# stirrer.net
KiCad netlist of a schematic drawn in EAGLE
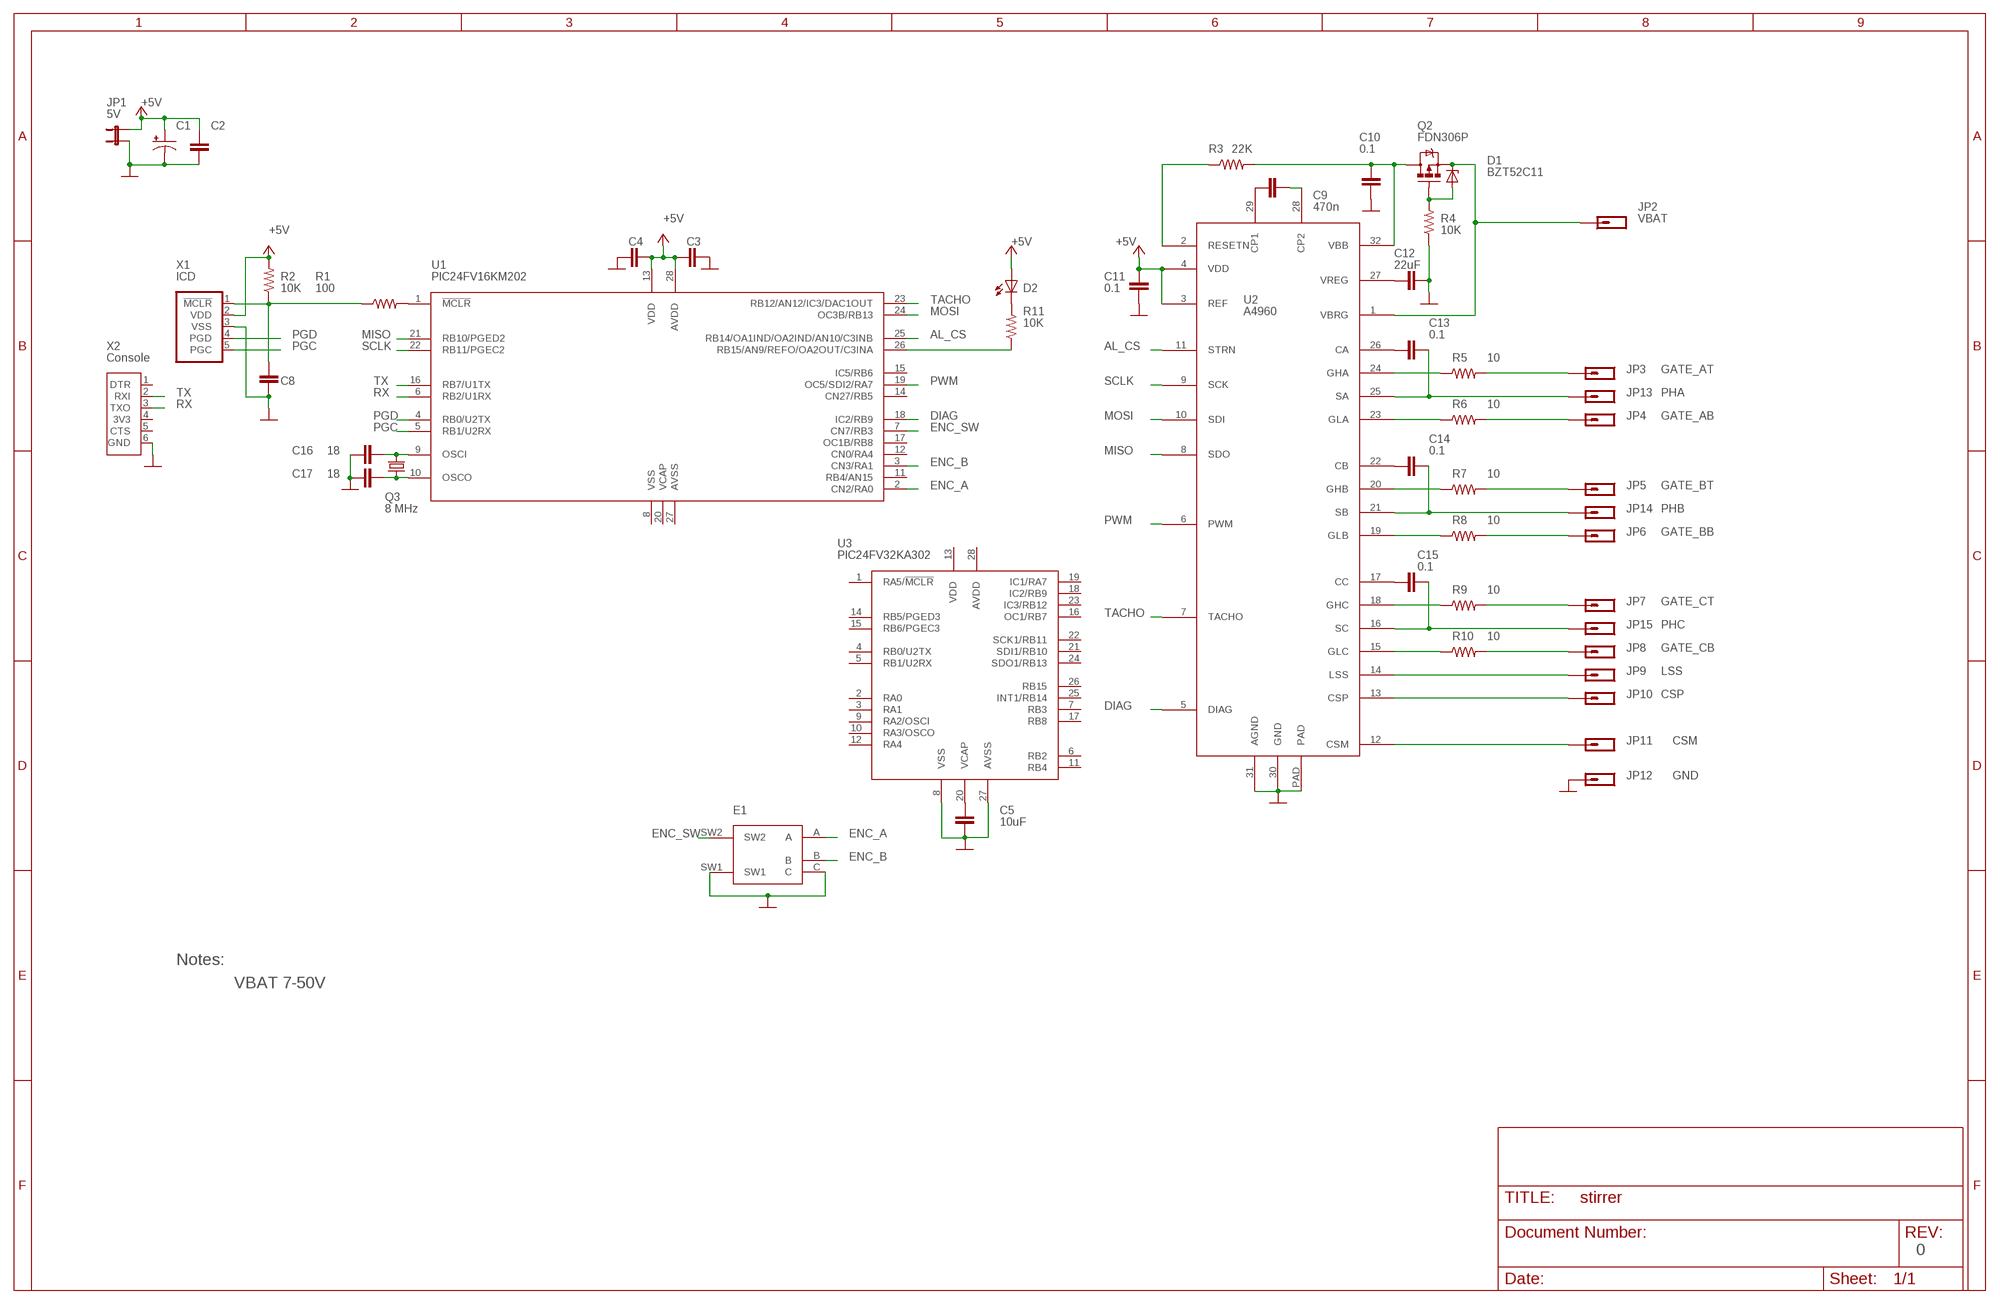
[diagram p0: schematic, sheet 1]

(export (version "E")
  (design (tool "Eeschema 10.0.6"))
  (components
    (comp (ref "C1")
      (value "CAP_POL-RAD8")
      (footprint "eagle-import:CAP_RAD_8MM")
      (libsource (lib "eagle-import") (part "CAP_POL-RAD8"))
    )
    (comp (ref "C2")
      (value "CAP0603")
      (footprint "eagle-import:0603")
      (libsource (lib "eagle-import") (part "CAP0603"))
    )
    (comp (ref "C3")
      (value "0.1uF")
      (footprint "eagle-import:0603")
      (libsource (lib "eagle-import") (part "C-0603"))
    )
    (comp (ref "C4")
      (value "0.1uF")
      (footprint "eagle-import:0603")
      (libsource (lib "eagle-import") (part "C-0603"))
    )
    (comp (ref "C5")
      (value "10uF")
      (footprint "eagle-import:0603")
      (libsource (lib "eagle-import") (part "C-0603"))
    )
    (comp (ref "C8")
      (value "0.1uF")
      (footprint "eagle-import:0603")
      (libsource (lib "eagle-import") (part "C-0603"))
    )
    (comp (ref "C9")
      (value "470n")
      (footprint "eagle-import:0603")
      (libsource (lib "eagle-import") (part "C-0603"))
    )
    (comp (ref "C10")
      (value "0.1")
      (footprint "eagle-import:0603")
      (libsource (lib "eagle-import") (part "C-0603"))
    )
    (comp (ref "C11")
      (value "0.1")
      (footprint "eagle-import:0603")
      (libsource (lib "eagle-import") (part "C-0603"))
    )
    (comp (ref "C12")
      (value "22uF")
      (footprint "eagle-import:1206")
      (libsource (lib "eagle-import") (part "CAP1206"))
    )
    (comp (ref "C13")
      (value "0.1")
      (footprint "eagle-import:0603")
      (libsource (lib "eagle-import") (part "C-0603"))
    )
    (comp (ref "C14")
      (value "0.1")
      (footprint "eagle-import:0603")
      (libsource (lib "eagle-import") (part "C-0603"))
    )
    (comp (ref "C15")
      (value "0.1")
      (footprint "eagle-import:0603")
      (libsource (lib "eagle-import") (part "C-0603"))
    )
    (comp (ref "C16")
      (value "18")
      (footprint "eagle-import:0603")
      (libsource (lib "eagle-import") (part "C-0603"))
    )
    (comp (ref "C17")
      (value "18")
      (footprint "eagle-import:0603")
      (libsource (lib "eagle-import") (part "C-0603"))
    )
    (comp (ref "D1")
      (value "BZT52C11")
      (footprint "eagle-import:SOD-123")
      (libsource (lib "eagle-import") (part "ZENER-SOD-123"))
    )
    (comp (ref "D2")
      (value "LED5MM")
      (footprint "eagle-import:LED5MM")
      (libsource (lib "eagle-import") (part "LED5MM"))
    )
    (comp (ref "E1")
      (value "ROTARY_ENCODER_SWITCH-LUT")
      (footprint "eagle-import:PEC12-LUT")
      (libsource (lib "eagle-import") (part "ROTARY_ENCODER_SWITCH-LUT"))
    )
    (comp (ref "JP1")
      (value "5V")
      (footprint "eagle-import:1X02")
      (libsource (lib "eagle-import") (part "JP1EPTH"))
    )
    (comp (ref "JP2")
      (value "VBAT")
      (footprint "eagle-import:1X01_TT")
      (libsource (lib "eagle-import") (part "M01-TT"))
    )
    (comp (ref "JP3")
      (value "GATE_AT")
      (footprint "eagle-import:1X01_TT")
      (libsource (lib "eagle-import") (part "M01-TT"))
    )
    (comp (ref "JP4")
      (value "GATE_AB")
      (footprint "eagle-import:1X01_TT")
      (libsource (lib "eagle-import") (part "M01-TT"))
    )
    (comp (ref "JP5")
      (value "GATE_BT")
      (footprint "eagle-import:1X01_TT")
      (libsource (lib "eagle-import") (part "M01-TT"))
    )
    (comp (ref "JP6")
      (value "GATE_BB")
      (footprint "eagle-import:1X01_TT")
      (libsource (lib "eagle-import") (part "M01-TT"))
    )
    (comp (ref "JP7")
      (value "GATE_CT")
      (footprint "eagle-import:1X01_TT")
      (libsource (lib "eagle-import") (part "M01-TT"))
    )
    (comp (ref "JP8")
      (value "GATE_CB")
      (footprint "eagle-import:1X01_TT")
      (libsource (lib "eagle-import") (part "M01-TT"))
    )
    (comp (ref "JP9")
      (value "LSS")
      (footprint "eagle-import:1X01_TT")
      (libsource (lib "eagle-import") (part "M01-TT"))
    )
    (comp (ref "JP10")
      (value "CSP")
      (footprint "eagle-import:1X01_TT")
      (libsource (lib "eagle-import") (part "M01-TT"))
    )
    (comp (ref "JP11")
      (value "CSM")
      (footprint "eagle-import:1X01_TT")
      (libsource (lib "eagle-import") (part "M01-TT"))
    )
    (comp (ref "JP12")
      (value "GND")
      (footprint "eagle-import:1X01_TT")
      (libsource (lib "eagle-import") (part "M01-TT"))
    )
    (comp (ref "JP13")
      (value "PHA")
      (footprint "eagle-import:1X01_TT")
      (libsource (lib "eagle-import") (part "M01-TT"))
    )
    (comp (ref "JP14")
      (value "PHB")
      (footprint "eagle-import:1X01_TT")
      (libsource (lib "eagle-import") (part "M01-TT"))
    )
    (comp (ref "JP15")
      (value "PHC")
      (footprint "eagle-import:1X01_TT")
      (libsource (lib "eagle-import") (part "M01-TT"))
    )
    (comp (ref "Q2")
      (value "FDN306P")
      (footprint "eagle-import:DPAK")
      (libsource (lib "eagle-import") (part "MOSFET-PCHANNEL-DPAK"))
    )
    (comp (ref "Q3")
      (value "8 MHz")
      (footprint "eagle-import:HC49US")
      (libsource (lib "eagle-import") (part "CRYSTAL_SFEHC49US"))
    )
    (comp (ref "R1")
      (value "100")
      (footprint "eagle-import:0603")
      (libsource (lib "eagle-import") (part "RESISTOR-0603"))
    )
    (comp (ref "R2")
      (value "10K")
      (footprint "eagle-import:0603")
      (libsource (lib "eagle-import") (part "RESISTOR-0603"))
    )
    (comp (ref "R3")
      (value "22K")
      (footprint "eagle-import:0603")
      (libsource (lib "eagle-import") (part "RESISTOR-0603"))
    )
    (comp (ref "R4")
      (value "10K")
      (footprint "eagle-import:0603")
      (libsource (lib "eagle-import") (part "RESISTOR-0603"))
    )
    (comp (ref "R5")
      (value "10")
      (footprint "eagle-import:0603")
      (libsource (lib "eagle-import") (part "RESISTOR-0603"))
    )
    (comp (ref "R6")
      (value "10")
      (footprint "eagle-import:0603")
      (libsource (lib "eagle-import") (part "RESISTOR-0603"))
    )
    (comp (ref "R7")
      (value "10")
      (footprint "eagle-import:0603")
      (libsource (lib "eagle-import") (part "RESISTOR-0603"))
    )
    (comp (ref "R8")
      (value "10")
      (footprint "eagle-import:0603")
      (libsource (lib "eagle-import") (part "RESISTOR-0603"))
    )
    (comp (ref "R9")
      (value "10")
      (footprint "eagle-import:0603")
      (libsource (lib "eagle-import") (part "RESISTOR-0603"))
    )
    (comp (ref "R10")
      (value "10")
      (footprint "eagle-import:0603")
      (libsource (lib "eagle-import") (part "RESISTOR-0603"))
    )
    (comp (ref "R11")
      (value "10K")
      (footprint "eagle-import:0603")
      (libsource (lib "eagle-import") (part "RESISTOR-0603"))
    )
    (comp (ref "U1")
      (value "PIC24FV16KM202")
      (footprint "eagle-import:DIL28-3")
      (libsource (lib "eagle-import") (part "PIC24FX16KM202-DIP"))
    )
    (comp (ref "U2")
      (value "A4960")
      (footprint "eagle-import:LQPF-32")
      (libsource (lib "eagle-import") (part "A4960"))
    )
    (comp (ref "U3")
      (value "PIC24FV32KA302")
      (footprint "eagle-import:DIL28-3")
      (libsource (lib "eagle-import") (part "PIC24FV32KA302_STIR-DIP"))
    )
    (comp (ref "X1")
      (value "ICD")
      (footprint "eagle-import:1X05-TT")
      (libsource (lib "eagle-import") (part "PIC_ICD-TT"))
    )
    (comp (ref "X2")
      (value "Console")
      (footprint "eagle-import:1X06TT")
      (libsource (lib "eagle-import") (part "SERIAL-SFTT"))
    )
  )
  (nets
    (net (code "1") (name "+5V") (class "Default")
      (node (ref "C1") (pin "P") (pinfunction "+_P") (pintype "passive"))
      (node (ref "C11") (pin "2") (pinfunction "2_2") (pintype "passive"))
      (node (ref "C2") (pin "1") (pinfunction "1_1") (pintype "passive"))
      (node (ref "C3") (pin "1") (pinfunction "1_1") (pintype "passive"))
      (node (ref "C4") (pin "2") (pinfunction "2_2") (pintype "passive"))
      (node (ref "D2") (pin "A") (pinfunction "A_A") (pintype "passive"))
      (node (ref "JP1") (pin "2") (pinfunction "2_2") (pintype "passive"))
      (node (ref "R2") (pin "2") (pinfunction "2_2") (pintype "passive"))
      (node (ref "U1") (pin "13") (pinfunction "VDD_13") (pintype "bidirectional"))
      (node (ref "U1") (pin "28") (pinfunction "AVDD_28") (pintype "bidirectional"))
      (node (ref "U2") (pin "3") (pinfunction "REF_3") (pintype "bidirectional"))
      (node (ref "U2") (pin "4") (pinfunction "VDD_4") (pintype "bidirectional"))
      (node (ref "X1") (pin "2") (pinfunction "VDD_2") (pintype "passive"))
    )
    (net (code "2") (name "/AL_CS") (class "Default")
      (node (ref "U1") (pin "25") (pinfunction "RB14/OA1IND/OA2IND/AN10/C3INB_25") (pintype "bidirectional"))
      (node (ref "U2") (pin "11") (pinfunction "STRN_11") (pintype "bidirectional"))
    )
    (net (code "3") (name "/DIAG") (class "Default")
      (node (ref "U1") (pin "18") (pinfunction "IC2/RB9_18") (pintype "bidirectional"))
      (node (ref "U2") (pin "5") (pinfunction "DIAG_5") (pintype "bidirectional"))
    )
    (net (code "4") (name "/ENC_A") (class "Default")
      (node (ref "E1") (pin "A") (pinfunction "A_A") (pintype "passive"))
      (node (ref "U1") (pin "2") (pinfunction "CN2/RA0_2") (pintype "bidirectional"))
    )
    (net (code "5") (name "/ENC_B") (class "Default")
      (node (ref "E1") (pin "B") (pinfunction "B_B") (pintype "passive"))
      (node (ref "U1") (pin "3") (pinfunction "CN3/RA1_3") (pintype "bidirectional"))
    )
    (net (code "6") (name "/ENC_SW") (class "Default")
      (node (ref "E1") (pin "SW2") (pinfunction "SW2_SW2") (pintype "passive"))
      (node (ref "U1") (pin "7") (pinfunction "CN7/RB3_7") (pintype "bidirectional"))
    )
    (net (code "7") (name "/MISO") (class "Default")
      (node (ref "U1") (pin "21") (pinfunction "RB10/PGED2_21") (pintype "bidirectional"))
      (node (ref "U2") (pin "8") (pinfunction "SDO_8") (pintype "bidirectional"))
    )
    (net (code "8") (name "/MOSI") (class "Default")
      (node (ref "U1") (pin "24") (pinfunction "OC3B/RB13_24") (pintype "bidirectional"))
      (node (ref "U2") (pin "10") (pinfunction "SDI_10") (pintype "bidirectional"))
    )
    (net (code "9") (name "/PGC") (class "Default")
      (node (ref "U1") (pin "5") (pinfunction "RB1/U2RX_5") (pintype "bidirectional"))
      (node (ref "X1") (pin "5") (pinfunction "PGC_5") (pintype "passive"))
    )
    (net (code "10") (name "/PGD") (class "Default")
      (node (ref "U1") (pin "4") (pinfunction "RB0/U2TX_4") (pintype "bidirectional"))
      (node (ref "X1") (pin "4") (pinfunction "PGD_4") (pintype "passive"))
    )
    (net (code "11") (name "/PWM") (class "Default")
      (node (ref "U1") (pin "19") (pinfunction "OC5/SDI2/RA7_19") (pintype "bidirectional"))
      (node (ref "U2") (pin "6") (pinfunction "PWM_6") (pintype "bidirectional"))
    )
    (net (code "12") (name "/RX") (class "Default")
      (node (ref "U1") (pin "6") (pinfunction "RB2/U1RX_6") (pintype "bidirectional"))
      (node (ref "X2") (pin "3") (pinfunction "TXO_3") (pintype "bidirectional"))
    )
    (net (code "13") (name "/SCLK") (class "Default")
      (node (ref "U1") (pin "22") (pinfunction "RB11/PGEC2_22") (pintype "bidirectional"))
      (node (ref "U2") (pin "9") (pinfunction "SCK_9") (pintype "bidirectional"))
    )
    (net (code "14") (name "/TACHO") (class "Default")
      (node (ref "U1") (pin "23") (pinfunction "RB12/AN12/IC3/DAC1OUT_23") (pintype "bidirectional"))
      (node (ref "U2") (pin "7") (pinfunction "TACHO_7") (pintype "bidirectional"))
    )
    (net (code "15") (name "/TX") (class "Default")
      (node (ref "U1") (pin "16") (pinfunction "RB7/U1TX_16") (pintype "bidirectional"))
      (node (ref "X2") (pin "2") (pinfunction "RXI_2") (pintype "bidirectional"))
    )
    (net (code "16") (name "GND") (class "Default")
      (node (ref "C1") (pin "N") (pinfunction "-_N") (pintype "passive"))
      (node (ref "C10") (pin "1") (pinfunction "1_1") (pintype "passive"))
      (node (ref "C11") (pin "1") (pinfunction "1_1") (pintype "passive"))
      (node (ref "C12") (pin "2") (pinfunction "2_2") (pintype "passive"))
      (node (ref "C16") (pin "1") (pinfunction "1_1") (pintype "passive"))
      (node (ref "C17") (pin "1") (pinfunction "1_1") (pintype "passive"))
      (node (ref "C2") (pin "2") (pinfunction "2_2") (pintype "passive"))
      (node (ref "C3") (pin "2") (pinfunction "2_2") (pintype "passive"))
      (node (ref "C4") (pin "1") (pinfunction "1_1") (pintype "passive"))
      (node (ref "C5") (pin "2") (pinfunction "2_2") (pintype "passive"))
      (node (ref "C8") (pin "1") (pinfunction "1_1") (pintype "passive"))
      (node (ref "E1") (pin "C") (pinfunction "C_C") (pintype "passive"))
      (node (ref "E1") (pin "SW1") (pinfunction "SW1_SW1") (pintype "passive"))
      (node (ref "JP1") (pin "1") (pinfunction "1_1") (pintype "passive"))
      (node (ref "JP12") (pin "1") (pinfunction "1_1") (pintype "passive"))
      (node (ref "R4") (pin "1") (pinfunction "1_1") (pintype "passive"))
      (node (ref "U2") (pin "30") (pinfunction "GND_30") (pintype "bidirectional"))
      (node (ref "U2") (pin "31") (pinfunction "AGND_31") (pintype "bidirectional"))
      (node (ref "U2") (pin "PAD") (pinfunction "PAD_PAD") (pintype "bidirectional"))
      (node (ref "U3") (pin "27") (pinfunction "AVSS_27") (pintype "bidirectional"))
      (node (ref "U3") (pin "8") (pinfunction "VSS_8") (pintype "bidirectional"))
      (node (ref "X1") (pin "3") (pinfunction "VSS_3") (pintype "passive"))
      (node (ref "X2") (pin "6") (pinfunction "GND_6") (pintype "bidirectional"))
    )
    (net (code "17") (name "Net-(D1-C)") (class "Default")
      (node (ref "D1") (pin "K") (pinfunction "C_K") (pintype "passive"))
      (node (ref "JP2") (pin "1") (pinfunction "1_1") (pintype "passive"))
      (node (ref "Q2") (pin "3") (pinfunction "S_3") (pintype "passive"))
      (node (ref "U2") (pin "1") (pinfunction "VBRG_1") (pintype "bidirectional"))
    )
    (net (code "18") (name "Net-(D2-C)") (class "Default")
      (node (ref "D2") (pin "K") (pinfunction "C_K") (pintype "passive"))
      (node (ref "R11") (pin "2") (pinfunction "2_2") (pintype "passive"))
    )
    (net (code "19") (name "Net-(JP3-Pad1)") (class "Default")
      (node (ref "JP3") (pin "1") (pinfunction "1_1") (pintype "passive"))
      (node (ref "R5") (pin "2") (pinfunction "2_2") (pintype "passive"))
    )
    (net (code "20") (name "Net-(JP4-Pad1)") (class "Default")
      (node (ref "JP4") (pin "1") (pinfunction "1_1") (pintype "passive"))
      (node (ref "R6") (pin "2") (pinfunction "2_2") (pintype "passive"))
    )
    (net (code "21") (name "Net-(JP5-Pad1)") (class "Default")
      (node (ref "JP5") (pin "1") (pinfunction "1_1") (pintype "passive"))
      (node (ref "R7") (pin "2") (pinfunction "2_2") (pintype "passive"))
    )
    (net (code "22") (name "Net-(JP6-Pad1)") (class "Default")
      (node (ref "JP6") (pin "1") (pinfunction "1_1") (pintype "passive"))
      (node (ref "R8") (pin "2") (pinfunction "2_2") (pintype "passive"))
    )
    (net (code "23") (name "Net-(JP7-Pad1)") (class "Default")
      (node (ref "JP7") (pin "1") (pinfunction "1_1") (pintype "passive"))
      (node (ref "R9") (pin "2") (pinfunction "2_2") (pintype "passive"))
    )
    (net (code "24") (name "Net-(JP8-Pad1)") (class "Default")
      (node (ref "JP8") (pin "1") (pinfunction "1_1") (pintype "passive"))
      (node (ref "R10") (pin "2") (pinfunction "2_2") (pintype "passive"))
    )
    (net (code "25") (name "Net-(Q2-D)") (class "Default")
      (node (ref "C10") (pin "2") (pinfunction "2_2") (pintype "passive"))
      (node (ref "Q2") (pin "4") (pinfunction "D_4") (pintype "passive"))
      (node (ref "R3") (pin "2") (pinfunction "2_2") (pintype "passive"))
      (node (ref "U2") (pin "32") (pinfunction "VBB_32") (pintype "bidirectional"))
    )
    (net (code "26") (name "Net-(Q2-G)") (class "Default")
      (node (ref "D1") (pin "A") (pinfunction "A_A") (pintype "passive"))
      (node (ref "Q2") (pin "1") (pinfunction "G_1") (pintype "passive"))
      (node (ref "R4") (pin "2") (pinfunction "2_2") (pintype "passive"))
    )
    (net (code "27") (name "Net-(U1-OSCI)") (class "Default")
      (node (ref "C16") (pin "2") (pinfunction "2_2") (pintype "passive"))
      (node (ref "Q3") (pin "2") (pinfunction "2_2") (pintype "passive"))
      (node (ref "U1") (pin "9") (pinfunction "OSCI_9") (pintype "bidirectional"))
    )
    (net (code "28") (name "Net-(U1-OSCO)") (class "Default")
      (node (ref "C17") (pin "2") (pinfunction "2_2") (pintype "passive"))
      (node (ref "Q3") (pin "1") (pinfunction "1_1") (pintype "passive"))
      (node (ref "U1") (pin "10") (pinfunction "OSCO_10") (pintype "bidirectional"))
    )
    (net (code "29") (name "Net-(U1-RB15{slash}AN9{slash}REFO{slash}OA2OUT{slash}C3INA)") (class "Default")
      (node (ref "R11") (pin "1") (pinfunction "1_1") (pintype "passive"))
      (node (ref "U1") (pin "26") (pinfunction "RB15/AN9/REFO/OA2OUT/C3INA_26") (pintype "bidirectional"))
    )
    (net (code "30") (name "Net-(U1-~{MCLR})") (class "Default")
      (node (ref "R1") (pin "2") (pinfunction "2_2") (pintype "passive"))
      (node (ref "U1") (pin "1") (pinfunction "~{MCLR}_1") (pintype "bidirectional"))
    )
    (net (code "31") (name "Net-(U2-CA)") (class "Default")
      (node (ref "C13") (pin "2") (pinfunction "2_2") (pintype "passive"))
      (node (ref "U2") (pin "26") (pinfunction "CA_26") (pintype "bidirectional"))
    )
    (net (code "32") (name "Net-(U2-CB)") (class "Default")
      (node (ref "C14") (pin "2") (pinfunction "2_2") (pintype "passive"))
      (node (ref "U2") (pin "22") (pinfunction "CB_22") (pintype "bidirectional"))
    )
    (net (code "33") (name "Net-(U2-CC)") (class "Default")
      (node (ref "C15") (pin "2") (pinfunction "2_2") (pintype "passive"))
      (node (ref "U2") (pin "17") (pinfunction "CC_17") (pintype "bidirectional"))
    )
    (net (code "34") (name "Net-(U2-CP1)") (class "Default")
      (node (ref "C9") (pin "1") (pinfunction "1_1") (pintype "passive"))
      (node (ref "U2") (pin "29") (pinfunction "CP1_29") (pintype "bidirectional"))
    )
    (net (code "35") (name "Net-(U2-CP2)") (class "Default")
      (node (ref "C9") (pin "2") (pinfunction "2_2") (pintype "passive"))
      (node (ref "U2") (pin "28") (pinfunction "CP2_28") (pintype "bidirectional"))
    )
    (net (code "36") (name "Net-(U2-CSM)") (class "Default")
      (node (ref "JP11") (pin "1") (pinfunction "1_1") (pintype "passive"))
      (node (ref "U2") (pin "12") (pinfunction "CSM_12") (pintype "bidirectional"))
    )
    (net (code "37") (name "Net-(U2-CSP)") (class "Default")
      (node (ref "JP10") (pin "1") (pinfunction "1_1") (pintype "passive"))
      (node (ref "U2") (pin "13") (pinfunction "CSP_13") (pintype "bidirectional"))
    )
    (net (code "38") (name "Net-(U2-GHA)") (class "Default")
      (node (ref "R5") (pin "1") (pinfunction "1_1") (pintype "passive"))
      (node (ref "U2") (pin "24") (pinfunction "GHA_24") (pintype "bidirectional"))
    )
    (net (code "39") (name "Net-(U2-GHB)") (class "Default")
      (node (ref "R7") (pin "1") (pinfunction "1_1") (pintype "passive"))
      (node (ref "U2") (pin "20") (pinfunction "GHB_20") (pintype "bidirectional"))
    )
    (net (code "40") (name "Net-(U2-GHC)") (class "Default")
      (node (ref "R9") (pin "1") (pinfunction "1_1") (pintype "passive"))
      (node (ref "U2") (pin "18") (pinfunction "GHC_18") (pintype "bidirectional"))
    )
    (net (code "41") (name "Net-(U2-GLA)") (class "Default")
      (node (ref "R6") (pin "1") (pinfunction "1_1") (pintype "passive"))
      (node (ref "U2") (pin "23") (pinfunction "GLA_23") (pintype "bidirectional"))
    )
    (net (code "42") (name "Net-(U2-GLB)") (class "Default")
      (node (ref "R8") (pin "1") (pinfunction "1_1") (pintype "passive"))
      (node (ref "U2") (pin "19") (pinfunction "GLB_19") (pintype "bidirectional"))
    )
    (net (code "43") (name "Net-(U2-GLC)") (class "Default")
      (node (ref "R10") (pin "1") (pinfunction "1_1") (pintype "passive"))
      (node (ref "U2") (pin "15") (pinfunction "GLC_15") (pintype "bidirectional"))
    )
    (net (code "44") (name "Net-(U2-LSS)") (class "Default")
      (node (ref "JP9") (pin "1") (pinfunction "1_1") (pintype "passive"))
      (node (ref "U2") (pin "14") (pinfunction "LSS_14") (pintype "bidirectional"))
    )
    (net (code "45") (name "Net-(U2-RESETN)") (class "Default")
      (node (ref "R3") (pin "1") (pinfunction "1_1") (pintype "passive"))
      (node (ref "U2") (pin "2") (pinfunction "RESETN_2") (pintype "bidirectional"))
    )
    (net (code "46") (name "Net-(U2-SA)") (class "Default")
      (node (ref "C13") (pin "1") (pinfunction "1_1") (pintype "passive"))
      (node (ref "JP13") (pin "1") (pinfunction "1_1") (pintype "passive"))
      (node (ref "U2") (pin "25") (pinfunction "SA_25") (pintype "bidirectional"))
    )
    (net (code "47") (name "Net-(U2-SB)") (class "Default")
      (node (ref "C14") (pin "1") (pinfunction "1_1") (pintype "passive"))
      (node (ref "JP14") (pin "1") (pinfunction "1_1") (pintype "passive"))
      (node (ref "U2") (pin "21") (pinfunction "SB_21") (pintype "bidirectional"))
    )
    (net (code "48") (name "Net-(U2-SC)") (class "Default")
      (node (ref "C15") (pin "1") (pinfunction "1_1") (pintype "passive"))
      (node (ref "JP15") (pin "1") (pinfunction "1_1") (pintype "passive"))
      (node (ref "U2") (pin "16") (pinfunction "SC_16") (pintype "bidirectional"))
    )
    (net (code "49") (name "Net-(U2-VREG)") (class "Default")
      (node (ref "C12") (pin "1") (pinfunction "1_1") (pintype "passive"))
      (node (ref "U2") (pin "27") (pinfunction "VREG_27") (pintype "bidirectional"))
    )
    (net (code "50") (name "Net-(U3-VCAP)") (class "Default")
      (node (ref "C5") (pin "1") (pinfunction "1_1") (pintype "passive"))
      (node (ref "U3") (pin "20") (pinfunction "VCAP_20") (pintype "bidirectional"))
    )
    (net (code "51") (name "Net-(X1-~{MCLR})") (class "Default")
      (node (ref "C8") (pin "2") (pinfunction "2_2") (pintype "passive"))
      (node (ref "R1") (pin "1") (pinfunction "1_1") (pintype "passive"))
      (node (ref "R2") (pin "1") (pinfunction "1_1") (pintype "passive"))
      (node (ref "X1") (pin "1") (pinfunction "~{MCLR}_1") (pintype "passive"))
    )
    (net (code "52") (name "unconnected-(U1-AVSS-Pad27)") (class "Default")
      (node (ref "U1") (pin "27") (pinfunction "AVSS_27") (pintype "bidirectional"))
    )
    (net (code "53") (name "unconnected-(U1-CN0{slash}RA4-Pad12)") (class "Default")
      (node (ref "U1") (pin "12") (pinfunction "CN0/RA4_12") (pintype "bidirectional"))
    )
    (net (code "54") (name "unconnected-(U1-CN27{slash}RB5-Pad14)") (class "Default")
      (node (ref "U1") (pin "14") (pinfunction "CN27/RB5_14") (pintype "bidirectional"))
    )
    (net (code "55") (name "unconnected-(U1-IC5{slash}RB6-Pad15)") (class "Default")
      (node (ref "U1") (pin "15") (pinfunction "IC5/RB6_15") (pintype "bidirectional"))
    )
    (net (code "56") (name "unconnected-(U1-OC1B{slash}RB8-Pad17)") (class "Default")
      (node (ref "U1") (pin "17") (pinfunction "OC1B/RB8_17") (pintype "bidirectional"))
    )
    (net (code "57") (name "unconnected-(U1-RB4{slash}AN15-Pad11)") (class "Default")
      (node (ref "U1") (pin "11") (pinfunction "RB4/AN15_11") (pintype "bidirectional"))
    )
    (net (code "58") (name "unconnected-(U1-VCAP-Pad20)") (class "Default")
      (node (ref "U1") (pin "20") (pinfunction "VCAP_20") (pintype "bidirectional"))
    )
    (net (code "59") (name "unconnected-(U1-VSS-Pad8)") (class "Default")
      (node (ref "U1") (pin "8") (pinfunction "VSS_8") (pintype "bidirectional"))
    )
    (net (code "60") (name "unconnected-(U3-AVDD-Pad28)") (class "Default")
      (node (ref "U3") (pin "28") (pinfunction "AVDD_28") (pintype "bidirectional"))
    )
    (net (code "61") (name "unconnected-(U3-IC1{slash}RA7-Pad19)") (class "Default")
      (node (ref "U3") (pin "19") (pinfunction "IC1/RA7_19") (pintype "bidirectional"))
    )
    (net (code "62") (name "unconnected-(U3-IC2{slash}RB9-Pad18)") (class "Default")
      (node (ref "U3") (pin "18") (pinfunction "IC2/RB9_18") (pintype "bidirectional"))
    )
    (net (code "63") (name "unconnected-(U3-IC3{slash}RB12-Pad23)") (class "Default")
      (node (ref "U3") (pin "23") (pinfunction "IC3/RB12_23") (pintype "bidirectional"))
    )
    (net (code "64") (name "unconnected-(U3-INT1{slash}RB14-Pad25)") (class "Default")
      (node (ref "U3") (pin "25") (pinfunction "INT1/RB14_25") (pintype "bidirectional"))
    )
    (net (code "65") (name "unconnected-(U3-OC1{slash}RB7-Pad16)") (class "Default")
      (node (ref "U3") (pin "16") (pinfunction "OC1/RB7_16") (pintype "bidirectional"))
    )
    (net (code "66") (name "unconnected-(U3-RA0-Pad2)") (class "Default")
      (node (ref "U3") (pin "2") (pinfunction "RA0_2") (pintype "bidirectional"))
    )
    (net (code "67") (name "unconnected-(U3-RA1-Pad3)") (class "Default")
      (node (ref "U3") (pin "3") (pinfunction "RA1_3") (pintype "bidirectional"))
    )
    (net (code "68") (name "unconnected-(U3-RA2{slash}OSCI-Pad9)") (class "Default")
      (node (ref "U3") (pin "9") (pinfunction "RA2/OSCI_9") (pintype "bidirectional"))
    )
    (net (code "69") (name "unconnected-(U3-RA3{slash}OSCO-Pad10)") (class "Default")
      (node (ref "U3") (pin "10") (pinfunction "RA3/OSCO_10") (pintype "bidirectional"))
    )
    (net (code "70") (name "unconnected-(U3-RA4-Pad12)") (class "Default")
      (node (ref "U3") (pin "12") (pinfunction "RA4_12") (pintype "bidirectional"))
    )
    (net (code "71") (name "unconnected-(U3-RA5{slash}~{MCLR}-Pad1)") (class "Default")
      (node (ref "U3") (pin "1") (pinfunction "RA5/~{MCLR}_1") (pintype "bidirectional"))
    )
    (net (code "72") (name "unconnected-(U3-RB0{slash}U2TX-Pad4)") (class "Default")
      (node (ref "U3") (pin "4") (pinfunction "RB0/U2TX_4") (pintype "bidirectional"))
    )
    (net (code "73") (name "unconnected-(U3-RB1{slash}U2RX-Pad5)") (class "Default")
      (node (ref "U3") (pin "5") (pinfunction "RB1/U2RX_5") (pintype "bidirectional"))
    )
    (net (code "74") (name "unconnected-(U3-RB2-Pad6)") (class "Default")
      (node (ref "U3") (pin "6") (pinfunction "RB2_6") (pintype "bidirectional"))
    )
    (net (code "75") (name "unconnected-(U3-RB3-Pad7)") (class "Default")
      (node (ref "U3") (pin "7") (pinfunction "RB3_7") (pintype "bidirectional"))
    )
    (net (code "76") (name "unconnected-(U3-RB4-Pad11)") (class "Default")
      (node (ref "U3") (pin "11") (pinfunction "RB4_11") (pintype "bidirectional"))
    )
    (net (code "77") (name "unconnected-(U3-RB5{slash}PGED3-Pad14)") (class "Default")
      (node (ref "U3") (pin "14") (pinfunction "RB5/PGED3_14") (pintype "bidirectional"))
    )
    (net (code "78") (name "unconnected-(U3-RB6{slash}PGEC3-Pad15)") (class "Default")
      (node (ref "U3") (pin "15") (pinfunction "RB6/PGEC3_15") (pintype "bidirectional"))
    )
    (net (code "79") (name "unconnected-(U3-RB8-Pad17)") (class "Default")
      (node (ref "U3") (pin "17") (pinfunction "RB8_17") (pintype "bidirectional"))
    )
    (net (code "80") (name "unconnected-(U3-RB15-Pad26)") (class "Default")
      (node (ref "U3") (pin "26") (pinfunction "RB15_26") (pintype "bidirectional"))
    )
    (net (code "81") (name "unconnected-(U3-SCK1{slash}RB11-Pad22)") (class "Default")
      (node (ref "U3") (pin "22") (pinfunction "SCK1/RB11_22") (pintype "bidirectional"))
    )
    (net (code "82") (name "unconnected-(U3-SDI1{slash}RB10-Pad21)") (class "Default")
      (node (ref "U3") (pin "21") (pinfunction "SDI1/RB10_21") (pintype "bidirectional"))
    )
    (net (code "83") (name "unconnected-(U3-SDO1{slash}RB13-Pad24)") (class "Default")
      (node (ref "U3") (pin "24") (pinfunction "SDO1/RB13_24") (pintype "bidirectional"))
    )
    (net (code "84") (name "unconnected-(U3-VDD-Pad13)") (class "Default")
      (node (ref "U3") (pin "13") (pinfunction "VDD_13") (pintype "bidirectional"))
    )
    (net (code "85") (name "unconnected-(X2-3V3-Pad4)") (class "Default")
      (node (ref "X2") (pin "4") (pinfunction "3V3_4") (pintype "bidirectional"))
    )
    (net (code "86") (name "unconnected-(X2-CTS-Pad5)") (class "Default")
      (node (ref "X2") (pin "5") (pinfunction "CTS_5") (pintype "bidirectional"))
    )
    (net (code "87") (name "unconnected-(X2-DTR-Pad1)") (class "Default")
      (node (ref "X2") (pin "1") (pinfunction "DTR_1") (pintype "bidirectional"))
    )
  )
)
